# untitled.net
KiCad netlist of a schematic drawn in EAGLE
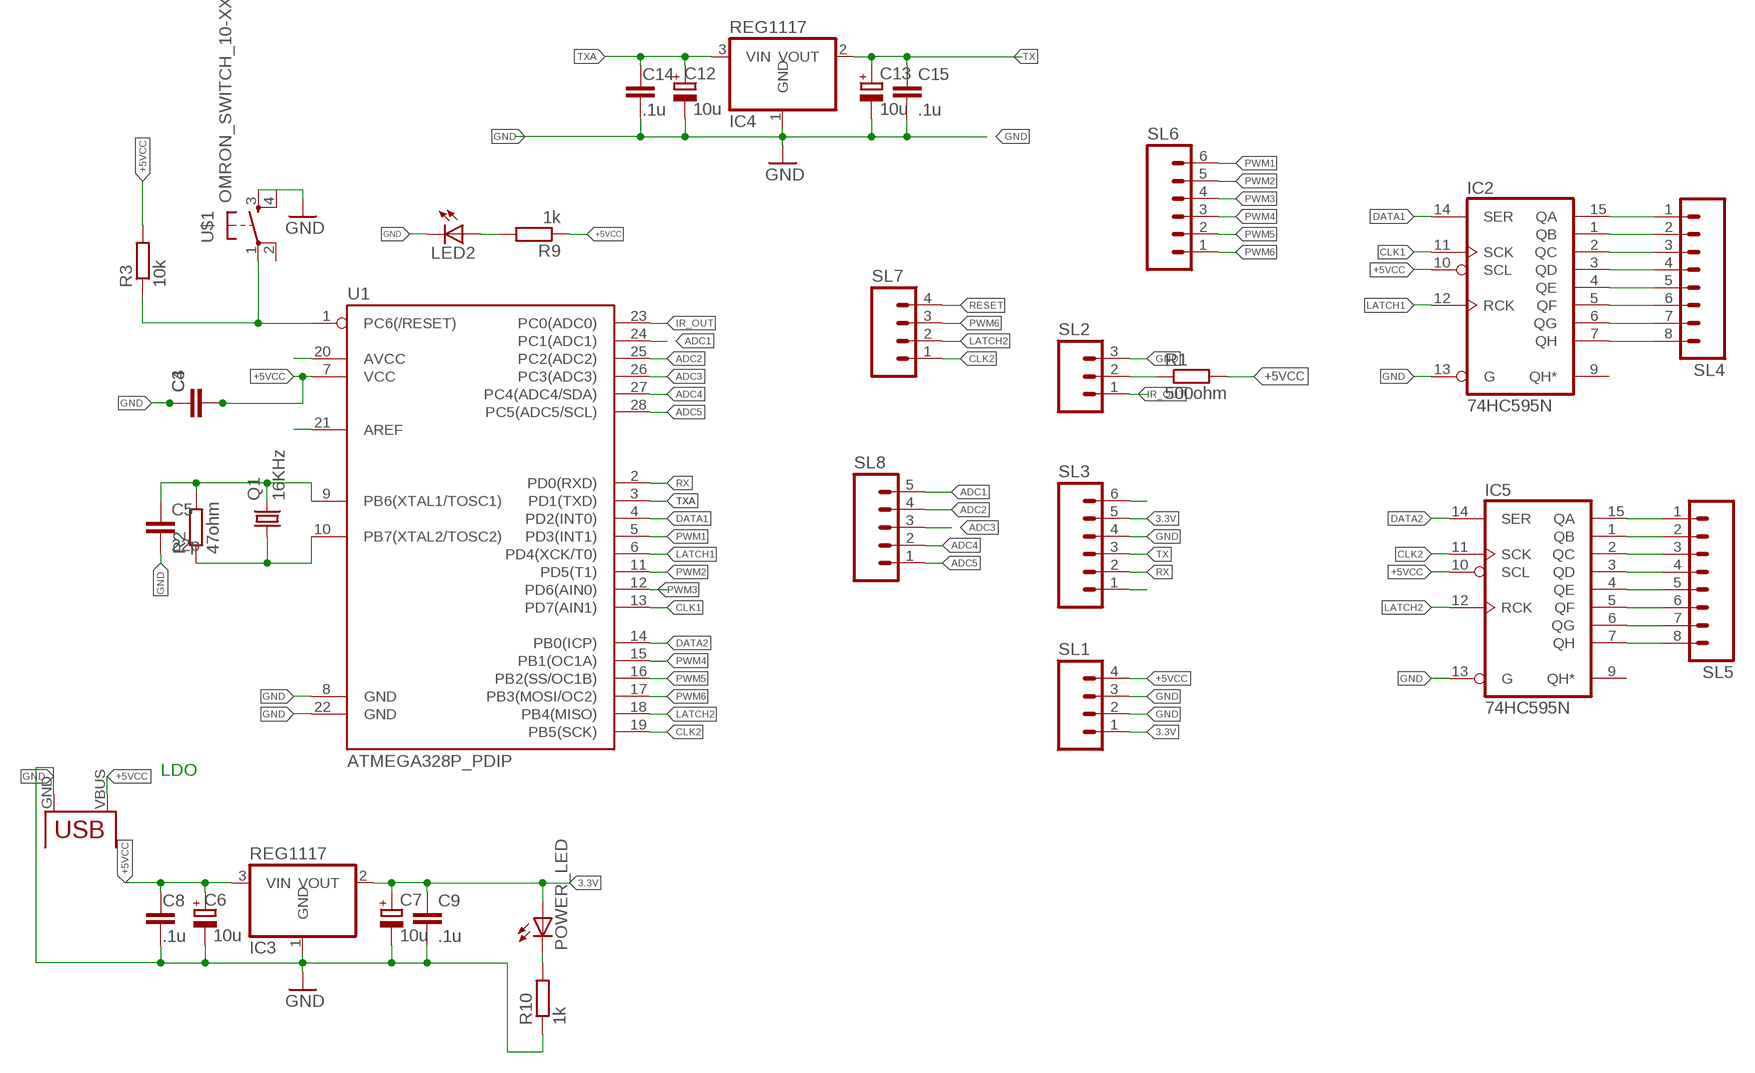
[diagram p0: schematic, sheet 1]

(export (version "E")
  (design (tool "Eeschema 10.0.6"))
  (components
    (comp (ref "C3")
      (value "C-EU025-025X050")
      (footprint "eagle-import:C025-025X050")
      (libsource (lib "eagle-import") (part "C-EU025-025X050"))
    )
    (comp (ref "C4")
      (value "C-EU025-025X050")
      (footprint "eagle-import:C025-025X050")
      (libsource (lib "eagle-import") (part "C-EU025-025X050"))
    )
    (comp (ref "C5")
      (value "22p")
      (footprint "eagle-import:C025-025X050")
      (libsource (lib "eagle-import") (part "rcl_C-EU025-025X050"))
    )
    (comp (ref "C6")
      (value "10u")
      (footprint "eagle-import:E2,5-5")
      (libsource (lib "eagle-import") (part "CPOL-EUE2.5-5"))
    )
    (comp (ref "C7")
      (value "10u")
      (footprint "eagle-import:E2,5-5")
      (libsource (lib "eagle-import") (part "CPOL-EUE2.5-5"))
    )
    (comp (ref "C8")
      (value ".1u")
      (footprint "eagle-import:C025-025X050")
      (libsource (lib "eagle-import") (part "cpo_sdjhjasjhasjf_C-EU025-025X050"))
    )
    (comp (ref "C9")
      (value ".1u")
      (footprint "eagle-import:C025-025X050")
      (libsource (lib "eagle-import") (part "cpo_sdjhjasjhasjf_C-EU025-025X050"))
    )
    (comp (ref "C12")
      (value "10u")
      (footprint "eagle-import:E2,5-5")
      (libsource (lib "eagle-import") (part "CPOL-EUE2.5-5"))
    )
    (comp (ref "C13")
      (value "10u")
      (footprint "eagle-import:E2,5-5")
      (libsource (lib "eagle-import") (part "CPOL-EUE2.5-5"))
    )
    (comp (ref "C14")
      (value ".1u")
      (footprint "eagle-import:C025-025X050")
      (libsource (lib "eagle-import") (part "cpo_sdjhjasjhasjf_C-EU025-025X050"))
    )
    (comp (ref "C15")
      (value ".1u")
      (footprint "eagle-import:C025-025X050")
      (libsource (lib "eagle-import") (part "cpo_sdjhjasjhasjf_C-EU025-025X050"))
    )
    (comp (ref "IC2")
      (value "74HC595N")
      (footprint "eagle-import:DIL16")
      (libsource (lib "eagle-import") (part "74595NHC"))
    )
    (comp (ref "IC3")
      (value "REG1117")
      (footprint "eagle-import:SOT223")
      (libsource (lib "eagle-import") (part "REG1117"))
    )
    (comp (ref "IC4")
      (value "REG1117")
      (footprint "eagle-import:SOT223")
      (libsource (lib "eagle-import") (part "REG1117"))
    )
    (comp (ref "IC5")
      (value "74HC595N")
      (footprint "eagle-import:DIL16")
      (libsource (lib "eagle-import") (part "74595NHC"))
    )
    (comp (ref "LED2")
      (value "LED3MM")
      (footprint "eagle-import:LED3MM")
      (libsource (lib "eagle-import") (part "LED3MM"))
    )
    (comp (ref "POWER_LED")
      (value "LED3MM")
      (footprint "eagle-import:LED3MM")
      (libsource (lib "eagle-import") (part "LED3MM"))
    )
    (comp (ref "Q1")
      (value "16KHz")
      (footprint "eagle-import:TC26H")
      (libsource (lib "eagle-import") (part "CRYSTALTC26H"))
    )
    (comp (ref "R1")
      (value "500ohm")
      (footprint "eagle-import:0207_7")
      (libsource (lib "eagle-import") (part "R-EU_0207/7"))
    )
    (comp (ref "R2")
      (value "47ohm")
      (footprint "eagle-import:0207_7")
      (libsource (lib "eagle-import") (part "R-EU_0207/7"))
    )
    (comp (ref "R3")
      (value "10k")
      (footprint "eagle-import:0207_7")
      (libsource (lib "eagle-import") (part "R-EU_0207/7"))
    )
    (comp (ref "R9")
      (value "1k")
      (footprint "eagle-import:0207_10")
      (libsource (lib "eagle-import") (part "resistor_R-EU_0207/10"))
    )
    (comp (ref "R10")
      (value "1k")
      (footprint "eagle-import:0207_7")
      (libsource (lib "eagle-import") (part "resistor_R-EU_0207/7"))
    )
    (comp (ref "SL1")
      (value "M04")
      (footprint "eagle-import:04P")
      (libsource (lib "eagle-import") (part "M04"))
    )
    (comp (ref "SL2")
      (value "M03")
      (footprint "eagle-import:03P")
      (libsource (lib "eagle-import") (part "M03"))
    )
    (comp (ref "SL3")
      (value "M06")
      (footprint "eagle-import:06P")
      (libsource (lib "eagle-import") (part "M06"))
    )
    (comp (ref "SL4")
      (value "M08")
      (footprint "eagle-import:08P")
      (libsource (lib "eagle-import") (part "M08"))
    )
    (comp (ref "SL5")
      (value "M08")
      (footprint "eagle-import:08P")
      (libsource (lib "eagle-import") (part "M08"))
    )
    (comp (ref "SL6")
      (value "M06")
      (footprint "eagle-import:06P")
      (libsource (lib "eagle-import") (part "M06"))
    )
    (comp (ref "SL7")
      (value "M04")
      (footprint "eagle-import:04P")
      (libsource (lib "eagle-import") (part "M04"))
    )
    (comp (ref "SL8")
      (value "M05")
      (footprint "eagle-import:05P")
      (libsource (lib "eagle-import") (part "M05"))
    )
    (comp (ref "U$1")
      (value "OMRON_SWITCH_10-XX")
      (footprint "eagle-import:B3F-10XX")
      (libsource (lib "eagle-import") (part "OMRON_SWITCH_10-XX"))
    )
    (comp (ref "U$2")
      (value "USB(POWER)")
      (footprint "eagle-import:USB(POWER)")
      (libsource (lib "eagle-import") (part "USB(POWER)"))
    )
    (comp (ref "U1")
      (value "ATMEGA328P_PDIP")
      (footprint "eagle-import:DIL28-3")
      (libsource (lib "eagle-import") (part "ATMEGA328P_PDIP"))
    )
  )
  (nets
    (net (code "1") (name "+5VCC") (class "Default")
      (node (ref "C3") (pin "2") (pinfunction "2_2") (pintype "passive"))
      (node (ref "C4") (pin "2") (pinfunction "2_2") (pintype "passive"))
      (node (ref "C6") (pin "+") (pinfunction "+_+") (pintype "passive"))
      (node (ref "C8") (pin "1") (pinfunction "1_1") (pintype "passive"))
      (node (ref "IC2") (pin "10") (pinfunction "SCL_10") (pintype "input"))
      (node (ref "IC3") (pin "3") (pinfunction "VIN_3") (pintype "input"))
      (node (ref "IC5") (pin "10") (pinfunction "SCL_10") (pintype "input"))
      (node (ref "R1") (pin "2") (pinfunction "2_2") (pintype "passive"))
      (node (ref "R3") (pin "2") (pinfunction "2_2") (pintype "passive"))
      (node (ref "R9") (pin "1") (pinfunction "1_1") (pintype "passive"))
      (node (ref "SL1") (pin "4") (pinfunction "4_4") (pintype "passive"))
      (node (ref "U$2") (pin "VBUS") (pinfunction "VCC_VBUS") (pintype "power_in"))
      (node (ref "U1") (pin "7") (pinfunction "VCC_7") (pintype "bidirectional"))
    )
    (net (code "2") (name "3.3V") (class "Default")
      (node (ref "C7") (pin "+") (pinfunction "+_+") (pintype "passive"))
      (node (ref "C9") (pin "1") (pinfunction "1_1") (pintype "passive"))
      (node (ref "IC3") (pin "2") (pinfunction "VOUT_2") (pintype "output"))
      (node (ref "POWER_LED") (pin "A") (pinfunction "A_A") (pintype "passive"))
      (node (ref "SL1") (pin "1") (pinfunction "1_1") (pintype "passive"))
      (node (ref "SL3") (pin "5") (pinfunction "5_5") (pintype "passive"))
    )
    (net (code "3") (name "ADC1") (class "Default")
      (node (ref "SL8") (pin "5") (pinfunction "5_5") (pintype "passive"))
      (node (ref "U1") (pin "24") (pinfunction "PC1(ADC1)_24") (pintype "bidirectional"))
    )
    (net (code "4") (name "ADC2") (class "Default")
      (node (ref "SL8") (pin "4") (pinfunction "4_4") (pintype "passive"))
      (node (ref "U1") (pin "25") (pinfunction "PC2(ADC2)_25") (pintype "bidirectional"))
    )
    (net (code "5") (name "ADC3") (class "Default")
      (node (ref "SL8") (pin "3") (pinfunction "3_3") (pintype "passive"))
      (node (ref "U1") (pin "26") (pinfunction "PC3(ADC3)_26") (pintype "bidirectional"))
    )
    (net (code "6") (name "ADC4") (class "Default")
      (node (ref "SL8") (pin "2") (pinfunction "2_2") (pintype "passive"))
      (node (ref "U1") (pin "27") (pinfunction "PC4(ADC4/SDA)_27") (pintype "bidirectional"))
    )
    (net (code "7") (name "ADC5") (class "Default")
      (node (ref "SL8") (pin "1") (pinfunction "1_1") (pintype "passive"))
      (node (ref "U1") (pin "28") (pinfunction "PC5(ADC5/SCL)_28") (pintype "bidirectional"))
    )
    (net (code "8") (name "CLK1") (class "Default")
      (node (ref "IC2") (pin "11") (pinfunction "SCK_11") (pintype "input"))
      (node (ref "U1") (pin "13") (pinfunction "PD7(AIN1)_13") (pintype "bidirectional"))
    )
    (net (code "9") (name "CLK2") (class "Default")
      (node (ref "IC5") (pin "11") (pinfunction "SCK_11") (pintype "input"))
      (node (ref "SL7") (pin "1") (pinfunction "1_1") (pintype "passive"))
      (node (ref "U1") (pin "19") (pinfunction "PB5(SCK)_19") (pintype "bidirectional"))
    )
    (net (code "10") (name "DATA1") (class "Default")
      (node (ref "IC2") (pin "14") (pinfunction "SER_14") (pintype "input"))
      (node (ref "U1") (pin "4") (pinfunction "PD2(INT0)_4") (pintype "bidirectional"))
    )
    (net (code "11") (name "DATA2") (class "Default")
      (node (ref "IC5") (pin "14") (pinfunction "SER_14") (pintype "input"))
      (node (ref "U1") (pin "14") (pinfunction "PB0(ICP)_14") (pintype "bidirectional"))
    )
    (net (code "12") (name "GND") (class "Default")
      (node (ref "C12") (pin "-") (pinfunction "-_-") (pintype "passive"))
      (node (ref "C13") (pin "-") (pinfunction "-_-") (pintype "passive"))
      (node (ref "C14") (pin "2") (pinfunction "2_2") (pintype "passive"))
      (node (ref "C15") (pin "2") (pinfunction "2_2") (pintype "passive"))
      (node (ref "C3") (pin "1") (pinfunction "1_1") (pintype "passive"))
      (node (ref "C4") (pin "1") (pinfunction "1_1") (pintype "passive"))
      (node (ref "C5") (pin "2") (pinfunction "2_2") (pintype "passive"))
      (node (ref "C6") (pin "-") (pinfunction "-_-") (pintype "passive"))
      (node (ref "C7") (pin "-") (pinfunction "-_-") (pintype "passive"))
      (node (ref "C8") (pin "2") (pinfunction "2_2") (pintype "passive"))
      (node (ref "C9") (pin "2") (pinfunction "2_2") (pintype "passive"))
      (node (ref "IC2") (pin "13") (pinfunction "G_13") (pintype "input"))
      (node (ref "IC3") (pin "1") (pinfunction "GND_1") (pintype "power_in"))
      (node (ref "IC4") (pin "1") (pinfunction "GND_1") (pintype "power_in"))
      (node (ref "IC5") (pin "13") (pinfunction "G_13") (pintype "input"))
      (node (ref "LED2") (pin "K") (pinfunction "C_K") (pintype "passive"))
      (node (ref "R10") (pin "1") (pinfunction "1_1") (pintype "passive"))
      (node (ref "SL1") (pin "2") (pinfunction "2_2") (pintype "passive"))
      (node (ref "SL1") (pin "3") (pinfunction "3_3") (pintype "passive"))
      (node (ref "SL2") (pin "3") (pinfunction "3_3") (pintype "passive"))
      (node (ref "SL3") (pin "4") (pinfunction "4_4") (pintype "passive"))
      (node (ref "U$1") (pin "3") (pinfunction "S_3") (pintype "passive"))
      (node (ref "U$2") (pin "GND") (pinfunction "GND_GND") (pintype "power_in"))
      (node (ref "U1") (pin "22") (pinfunction "GND_22") (pintype "bidirectional"))
      (node (ref "U1") (pin "8") (pinfunction "GND_8") (pintype "bidirectional"))
    )
    (net (code "13") (name "IR_OUT") (class "Default")
      (node (ref "SL2") (pin "1") (pinfunction "1_1") (pintype "passive"))
      (node (ref "U1") (pin "23") (pinfunction "PC0(ADC0)_23") (pintype "bidirectional"))
    )
    (net (code "14") (name "LATCH1") (class "Default")
      (node (ref "IC2") (pin "12") (pinfunction "RCK_12") (pintype "input"))
      (node (ref "U1") (pin "6") (pinfunction "PD4(XCK/T0)_6") (pintype "bidirectional"))
    )
    (net (code "15") (name "LATCH2") (class "Default")
      (node (ref "IC5") (pin "12") (pinfunction "RCK_12") (pintype "input"))
      (node (ref "SL7") (pin "2") (pinfunction "2_2") (pintype "passive"))
      (node (ref "U1") (pin "18") (pinfunction "PB4(MISO)_18") (pintype "bidirectional"))
    )
    (net (code "16") (name "Net-(IC2A-QA)") (class "Default")
      (node (ref "IC2") (pin "15") (pinfunction "QA_15") (pintype "tri_state"))
      (node (ref "SL4") (pin "1") (pinfunction "1_1") (pintype "passive"))
    )
    (net (code "17") (name "Net-(IC2A-QB)") (class "Default")
      (node (ref "IC2") (pin "1") (pinfunction "QB_1") (pintype "tri_state"))
      (node (ref "SL4") (pin "2") (pinfunction "2_2") (pintype "passive"))
    )
    (net (code "18") (name "Net-(IC2A-QC)") (class "Default")
      (node (ref "IC2") (pin "2") (pinfunction "QC_2") (pintype "tri_state"))
      (node (ref "SL4") (pin "3") (pinfunction "3_3") (pintype "passive"))
    )
    (net (code "19") (name "Net-(IC2A-QD)") (class "Default")
      (node (ref "IC2") (pin "3") (pinfunction "QD_3") (pintype "tri_state"))
      (node (ref "SL4") (pin "4") (pinfunction "4_4") (pintype "passive"))
    )
    (net (code "20") (name "Net-(IC2A-QE)") (class "Default")
      (node (ref "IC2") (pin "4") (pinfunction "QE_4") (pintype "tri_state"))
      (node (ref "SL4") (pin "5") (pinfunction "5_5") (pintype "passive"))
    )
    (net (code "21") (name "Net-(IC2A-QF)") (class "Default")
      (node (ref "IC2") (pin "5") (pinfunction "QF_5") (pintype "tri_state"))
      (node (ref "SL4") (pin "6") (pinfunction "6_6") (pintype "passive"))
    )
    (net (code "22") (name "Net-(IC2A-QG)") (class "Default")
      (node (ref "IC2") (pin "6") (pinfunction "QG_6") (pintype "tri_state"))
      (node (ref "SL4") (pin "7") (pinfunction "7_7") (pintype "passive"))
    )
    (net (code "23") (name "Net-(IC2A-QH)") (class "Default")
      (node (ref "IC2") (pin "7") (pinfunction "QH_7") (pintype "tri_state"))
      (node (ref "SL4") (pin "8") (pinfunction "8_8") (pintype "passive"))
    )
    (net (code "24") (name "Net-(IC5A-QA)") (class "Default")
      (node (ref "IC5") (pin "15") (pinfunction "QA_15") (pintype "tri_state"))
      (node (ref "SL5") (pin "1") (pinfunction "1_1") (pintype "passive"))
    )
    (net (code "25") (name "Net-(IC5A-QB)") (class "Default")
      (node (ref "IC5") (pin "1") (pinfunction "QB_1") (pintype "tri_state"))
      (node (ref "SL5") (pin "2") (pinfunction "2_2") (pintype "passive"))
    )
    (net (code "26") (name "Net-(IC5A-QC)") (class "Default")
      (node (ref "IC5") (pin "2") (pinfunction "QC_2") (pintype "tri_state"))
      (node (ref "SL5") (pin "3") (pinfunction "3_3") (pintype "passive"))
    )
    (net (code "27") (name "Net-(IC5A-QD)") (class "Default")
      (node (ref "IC5") (pin "3") (pinfunction "QD_3") (pintype "tri_state"))
      (node (ref "SL5") (pin "4") (pinfunction "4_4") (pintype "passive"))
    )
    (net (code "28") (name "Net-(IC5A-QE)") (class "Default")
      (node (ref "IC5") (pin "4") (pinfunction "QE_4") (pintype "tri_state"))
      (node (ref "SL5") (pin "5") (pinfunction "5_5") (pintype "passive"))
    )
    (net (code "29") (name "Net-(IC5A-QF)") (class "Default")
      (node (ref "IC5") (pin "5") (pinfunction "QF_5") (pintype "tri_state"))
      (node (ref "SL5") (pin "6") (pinfunction "6_6") (pintype "passive"))
    )
    (net (code "30") (name "Net-(IC5A-QG)") (class "Default")
      (node (ref "IC5") (pin "6") (pinfunction "QG_6") (pintype "tri_state"))
      (node (ref "SL5") (pin "7") (pinfunction "7_7") (pintype "passive"))
    )
    (net (code "31") (name "Net-(IC5A-QH)") (class "Default")
      (node (ref "IC5") (pin "7") (pinfunction "QH_7") (pintype "tri_state"))
      (node (ref "SL5") (pin "8") (pinfunction "8_8") (pintype "passive"))
    )
    (net (code "32") (name "Net-(LED2-PadA)") (class "Default")
      (node (ref "LED2") (pin "A") (pinfunction "A_A") (pintype "passive"))
      (node (ref "R9") (pin "2") (pinfunction "2_2") (pintype "passive"))
    )
    (net (code "33") (name "Net-(POWER_LED-C)") (class "Default")
      (node (ref "POWER_LED") (pin "K") (pinfunction "C_K") (pintype "passive"))
      (node (ref "R10") (pin "2") (pinfunction "2_2") (pintype "passive"))
    )
    (net (code "34") (name "Net-(R1-Pad1)") (class "Default")
      (node (ref "R1") (pin "1") (pinfunction "1_1") (pintype "passive"))
      (node (ref "SL2") (pin "2") (pinfunction "2_2") (pintype "passive"))
    )
    (net (code "35") (name "Net-(U1-PB6(XTAL1{slash}TOSC1))") (class "Default")
      (node (ref "C5") (pin "1") (pinfunction "1_1") (pintype "passive"))
      (node (ref "Q1") (pin "2") (pinfunction "2_2") (pintype "passive"))
      (node (ref "R2") (pin "2") (pinfunction "2_2") (pintype "passive"))
      (node (ref "U1") (pin "9") (pinfunction "PB6(XTAL1/TOSC1)_9") (pintype "bidirectional"))
    )
    (net (code "36") (name "Net-(U1-PB7(XTAL2{slash}TOSC2))") (class "Default")
      (node (ref "Q1") (pin "1") (pinfunction "1_1") (pintype "passive"))
      (node (ref "R2") (pin "1") (pinfunction "1_1") (pintype "passive"))
      (node (ref "U1") (pin "10") (pinfunction "PB7(XTAL2/TOSC2)_10") (pintype "bidirectional"))
    )
    (net (code "37") (name "PWM1") (class "Default")
      (node (ref "SL6") (pin "6") (pinfunction "6_6") (pintype "passive"))
      (node (ref "U1") (pin "5") (pinfunction "PD3(INT1)_5") (pintype "bidirectional"))
    )
    (net (code "38") (name "PWM2") (class "Default")
      (node (ref "SL6") (pin "5") (pinfunction "5_5") (pintype "passive"))
      (node (ref "U1") (pin "11") (pinfunction "PD5(T1)_11") (pintype "bidirectional"))
    )
    (net (code "39") (name "PWM3") (class "Default")
      (node (ref "SL6") (pin "4") (pinfunction "4_4") (pintype "passive"))
      (node (ref "U1") (pin "12") (pinfunction "PD6(AIN0)_12") (pintype "bidirectional"))
    )
    (net (code "40") (name "PWM4") (class "Default")
      (node (ref "SL6") (pin "3") (pinfunction "3_3") (pintype "passive"))
      (node (ref "U1") (pin "15") (pinfunction "PB1(OC1A)_15") (pintype "bidirectional"))
    )
    (net (code "41") (name "PWM5") (class "Default")
      (node (ref "SL6") (pin "2") (pinfunction "2_2") (pintype "passive"))
      (node (ref "U1") (pin "16") (pinfunction "PB2(SS/OC1B)_16") (pintype "bidirectional"))
    )
    (net (code "42") (name "PWM6") (class "Default")
      (node (ref "SL6") (pin "1") (pinfunction "1_1") (pintype "passive"))
      (node (ref "SL7") (pin "3") (pinfunction "3_3") (pintype "passive"))
      (node (ref "U1") (pin "17") (pinfunction "PB3(MOSI/OC2)_17") (pintype "bidirectional"))
    )
    (net (code "43") (name "RESET") (class "Default")
      (node (ref "R3") (pin "1") (pinfunction "1_1") (pintype "passive"))
      (node (ref "SL7") (pin "4") (pinfunction "4_4") (pintype "passive"))
      (node (ref "U$1") (pin "1") (pinfunction "P_1") (pintype "passive"))
      (node (ref "U1") (pin "1") (pinfunction "PC6(/RESET)_1") (pintype "bidirectional"))
    )
    (net (code "44") (name "RX") (class "Default")
      (node (ref "SL3") (pin "2") (pinfunction "2_2") (pintype "passive"))
      (node (ref "U1") (pin "2") (pinfunction "PD0(RXD)_2") (pintype "bidirectional"))
    )
    (net (code "45") (name "TX") (class "Default")
      (node (ref "C13") (pin "+") (pinfunction "+_+") (pintype "passive"))
      (node (ref "C15") (pin "1") (pinfunction "1_1") (pintype "passive"))
      (node (ref "IC4") (pin "2") (pinfunction "VOUT_2") (pintype "output"))
      (node (ref "SL3") (pin "3") (pinfunction "3_3") (pintype "passive"))
    )
    (net (code "46") (name "TXA") (class "Default")
      (node (ref "C12") (pin "+") (pinfunction "+_+") (pintype "passive"))
      (node (ref "C14") (pin "1") (pinfunction "1_1") (pintype "passive"))
      (node (ref "IC4") (pin "3") (pinfunction "VIN_3") (pintype "input"))
      (node (ref "U1") (pin "3") (pinfunction "PD1(TXD)_3") (pintype "bidirectional"))
    )
    (net (code "47") (name "unconnected-(IC2A-QH*-Pad9)") (class "Default")
      (node (ref "IC2") (pin "9") (pinfunction "QH*_9") (pintype "tri_state"))
    )
    (net (code "48") (name "unconnected-(IC5A-QH*-Pad9)") (class "Default")
      (node (ref "IC5") (pin "9") (pinfunction "QH*_9") (pintype "tri_state"))
    )
    (net (code "49") (name "unconnected-(SL3-Pad1)") (class "Default")
      (node (ref "SL3") (pin "1") (pinfunction "1_1") (pintype "passive"))
    )
    (net (code "50") (name "unconnected-(SL3-Pad6)") (class "Default")
      (node (ref "SL3") (pin "6") (pinfunction "6_6") (pintype "passive"))
    )
    (net (code "51") (name "unconnected-(U$1-P1-Pad2)") (class "Default")
      (node (ref "U$1") (pin "2") (pinfunction "P1_2") (pintype "passive"))
    )
    (net (code "52") (name "unconnected-(U$1-S1-Pad4)") (class "Default")
      (node (ref "U$1") (pin "4") (pinfunction "S1_4") (pintype "passive"))
    )
    (net (code "53") (name "unconnected-(U1-AREF-Pad21)") (class "Default")
      (node (ref "U1") (pin "21") (pinfunction "AREF_21") (pintype "bidirectional"))
    )
    (net (code "54") (name "unconnected-(U1-AVCC-Pad20)") (class "Default")
      (node (ref "U1") (pin "20") (pinfunction "AVCC_20") (pintype "bidirectional"))
    )
  )
)
